# Sheet5.net
KiCad netlist of a schematic drawn in Altium Designer
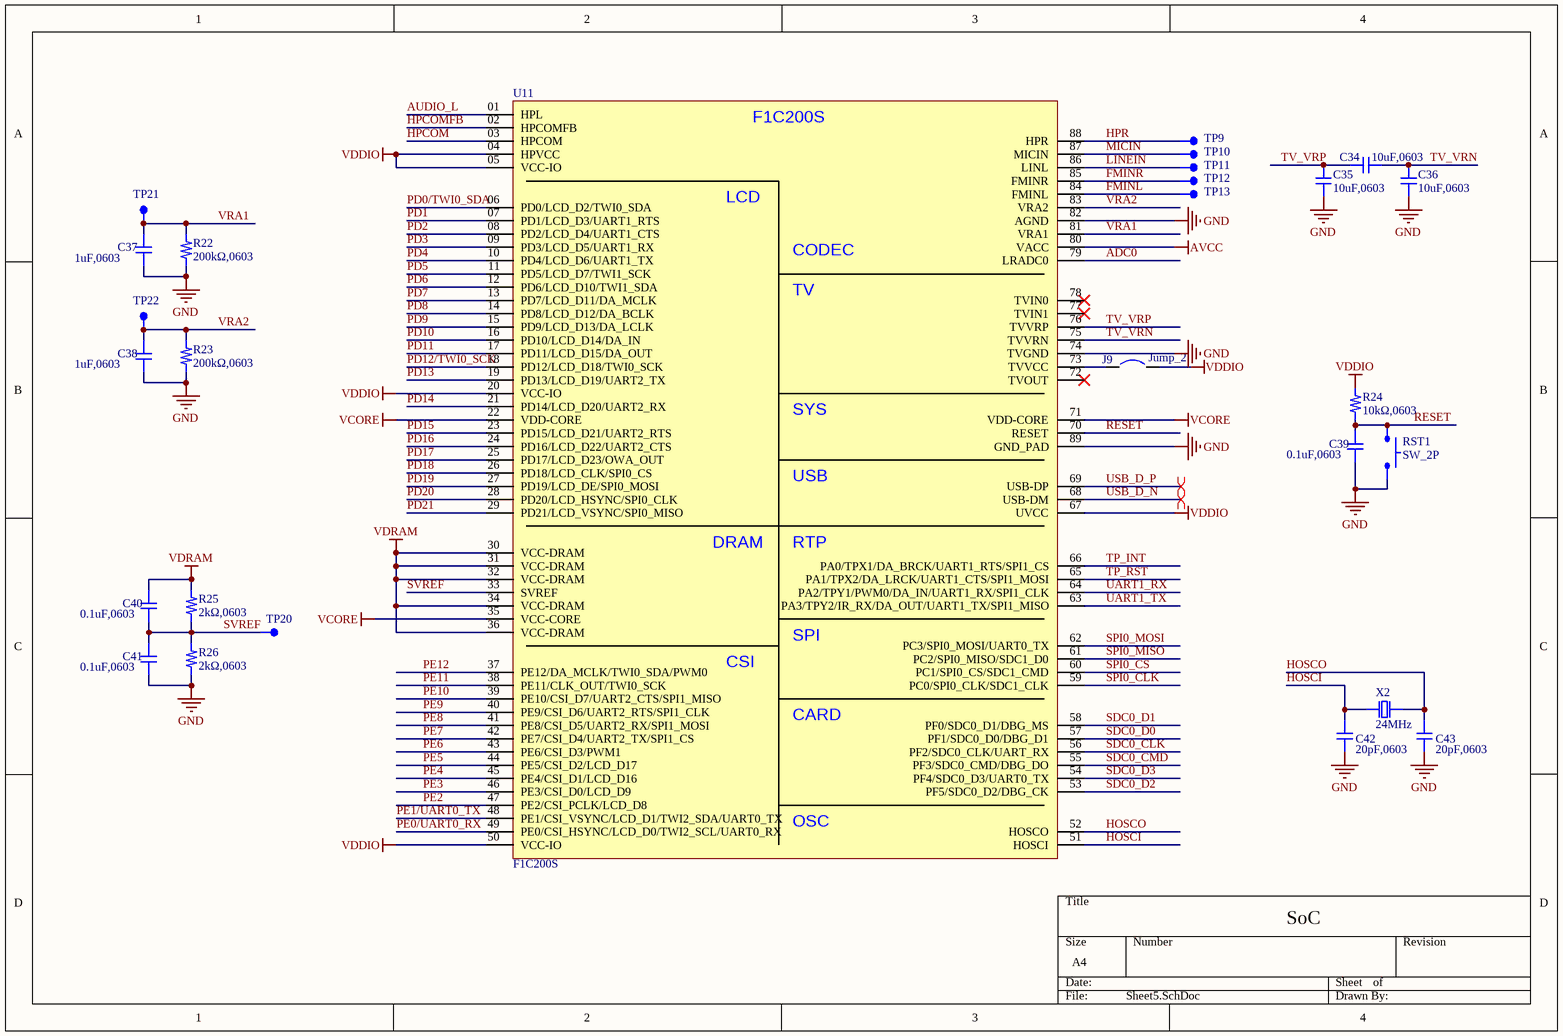
[diagram p0: Sheet5.SchDoc]

(export (version "E")
  (design (tool "Eeschema 10.0.6"))
  (components
    (comp (ref "C34") (value "10uF,0603") (footprint "C0603") (libsource (lib "myLib1") (part "Cap")))
    (comp (ref "C35") (value "10uF,0603") (footprint "C0603") (libsource (lib "myLib1") (part "Cap")))
    (comp (ref "C36") (value "10uF,0603") (footprint "C0603") (libsource (lib "myLib1") (part "Cap")))
    (comp (ref "C37") (value "1uF,0603") (footprint "C0603") (libsource (lib "myLib1") (part "Cap")))
    (comp (ref "C38") (value "1uF,0603") (footprint "C0603") (libsource (lib "myLib1") (part "Cap")))
    (comp (ref "C39") (value "0.1uF,0603") (footprint "C0603") (libsource (lib "myLib1") (part "Cap")))
    (comp (ref "C40") (value "0.1uF,0603") (footprint "C0603") (libsource (lib "myLib1") (part "Cap")))
    (comp (ref "C41") (value "0.1uF,0603") (footprint "C0603") (libsource (lib "myLib1") (part "Cap")))
    (comp (ref "C42") (value "20pF,0603") (footprint "C0603") (libsource (lib "myLib1") (part "Cap")))
    (comp (ref "C43") (value "20pF,0603") (footprint "C0603") (libsource (lib "myLib1") (part "Cap")))
    (comp (ref "J9") (value "Jump_2") (footprint "Jp_small") (libsource (lib "myLib1") (part "Jump_2")))
    (comp (ref "R22") (value "200kΩ,0603") (footprint "R0603") (libsource (lib "myLib1") (part "Res")))
    (comp (ref "R23") (value "200kΩ,0603") (footprint "R0603") (libsource (lib "myLib1") (part "Res")))
    (comp (ref "R24") (value "10kΩ,0603") (footprint "R0603") (libsource (lib "myLib1") (part "Res")))
    (comp (ref "R25") (value "2kΩ,0603") (footprint "R0603") (libsource (lib "myLib1") (part "Res")))
    (comp (ref "R26") (value "2kΩ,0603") (footprint "R0603") (libsource (lib "myLib1") (part "Res")))
    (comp (ref "RST1") (value "SW_2P") (footprint "SW_2P_4") (libsource (lib "myLib1") (part "SW_2P")))
    (comp (ref "TP9") (value "TP") (footprint "TP") (libsource (lib "myLib1") (part "TP")))
    (comp (ref "TP10") (value "TP") (footprint "TP") (libsource (lib "myLib1") (part "TP")))
    (comp (ref "TP11") (value "TP") (footprint "TP") (libsource (lib "myLib1") (part "TP")))
    (comp (ref "TP12") (value "TP") (footprint "TP") (libsource (lib "myLib1") (part "TP")))
    (comp (ref "TP13") (value "TP") (footprint "TP") (libsource (lib "myLib1") (part "TP")))
    (comp (ref "TP20") (value "TP") (footprint "TP") (libsource (lib "myLib1") (part "TP")))
    (comp (ref "TP21") (value "TP") (footprint "TP") (libsource (lib "myLib1") (part "TP")))
    (comp (ref "TP22") (value "TP") (footprint "TP") (libsource (lib "myLib1") (part "TP")))
    (comp (ref "U11")
      (value "F1C200S")
      (footprint "MQFN_10_10_v3")
      (libsource (lib "myLib1") (part "F1C200S"))
    )
    (comp (ref "X2") (value "24MHz") (footprint "XTAL_SMD_3225") (libsource (lib "myLib1") (part "XTAL")))
  )
  (nets
    (net (code "1") (name "/ADC0") (class "Default")
      (node (ref "U11") (pin "79") (pinfunction "LRADC0_79") (pintype "passive"))
    )
    (net (code "2") (name "/AUDIO_L") (class "Default")
      (node (ref "U11") (pin "01") (pinfunction "HPL_01") (pintype "passive"))
    )
    (net (code "3") (name "/FMINL") (class "Default")
      (node (ref "TP13") (pin "01") (pintype "passive"))
      (node (ref "U11") (pin "84") (pinfunction "FMINL_84") (pintype "passive"))
    )
    (net (code "4") (name "/FMINR") (class "Default")
      (node (ref "TP12") (pin "01") (pintype "passive"))
      (node (ref "U11") (pin "85") (pinfunction "FMINR_85") (pintype "passive"))
    )
    (net (code "5") (name "/HOSCI") (class "Default")
      (node (ref "C42") (pin "02") (pintype "passive"))
      (node (ref "U11") (pin "51") (pinfunction "HOSCI_51") (pintype "passive"))
      (node (ref "X2") (pin "01") (pinfunction "01_01") (pintype "passive"))
    )
    (net (code "6") (name "/HOSCO") (class "Default")
      (node (ref "C43") (pin "02") (pintype "passive"))
      (node (ref "U11") (pin "52") (pinfunction "HOSCO_52") (pintype "passive"))
      (node (ref "X2") (pin "02") (pinfunction "02_02") (pintype "passive"))
    )
    (net (code "7") (name "/HPCOM") (class "Default")
      (node (ref "U11") (pin "03") (pinfunction "HPCOM_03") (pintype "passive"))
    )
    (net (code "8") (name "/HPCOMFB") (class "Default")
      (node (ref "U11") (pin "02") (pinfunction "HPCOMFB_02") (pintype "passive"))
    )
    (net (code "9") (name "/HPR") (class "Default")
      (node (ref "TP9") (pin "01") (pintype "passive"))
      (node (ref "U11") (pin "88") (pinfunction "HPR_88") (pintype "passive"))
    )
    (net (code "10") (name "/LINEIN") (class "Default")
      (node (ref "TP11") (pin "01") (pintype "passive"))
      (node (ref "U11") (pin "86") (pinfunction "LINL_86") (pintype "passive"))
    )
    (net (code "11") (name "/MICIN") (class "Default")
      (node (ref "TP10") (pin "01") (pintype "passive"))
      (node (ref "U11") (pin "87") (pinfunction "MICIN_87") (pintype "passive"))
    )
    (net (code "12") (name "/PD0{slash}TWI0_SDA") (class "Default")
      (node (ref "U11") (pin "06") (pinfunction "PD0/LCD_D2/TWI0_SDA_06") (pintype "passive"))
    )
    (net (code "13") (name "/PD1") (class "Default")
      (node (ref "U11") (pin "07") (pinfunction "PD1/LCD_D3/UART1_RTS_07") (pintype "passive"))
    )
    (net (code "14") (name "/PD2") (class "Default")
      (node (ref "U11") (pin "08") (pinfunction "PD2/LCD_D4/UART1_CTS_08") (pintype "passive"))
    )
    (net (code "15") (name "/PD3") (class "Default")
      (node (ref "U11") (pin "09") (pinfunction "PD3/LCD_D5/UART1_RX_09") (pintype "passive"))
    )
    (net (code "16") (name "/PD4") (class "Default")
      (node (ref "U11") (pin "10") (pinfunction "PD4/LCD_D6/UART1_TX_10") (pintype "passive"))
    )
    (net (code "17") (name "/PD5") (class "Default")
      (node (ref "U11") (pin "11") (pinfunction "PD5/LCD_D7/TWI1_SCK_11") (pintype "passive"))
    )
    (net (code "18") (name "/PD6") (class "Default")
      (node (ref "U11") (pin "12") (pinfunction "PD6/LCD_D10/TWI1_SDA_12") (pintype "passive"))
    )
    (net (code "19") (name "/PD7") (class "Default")
      (node (ref "U11") (pin "13") (pinfunction "PD7/LCD_D11/DA_MCLK_13") (pintype "passive"))
    )
    (net (code "20") (name "/PD8") (class "Default")
      (node (ref "U11") (pin "14") (pinfunction "PD8/LCD_D12/DA_BCLK_14") (pintype "passive"))
    )
    (net (code "21") (name "/PD9") (class "Default")
      (node (ref "U11") (pin "15") (pinfunction "PD9/LCD_D13/DA_LCLK_15") (pintype "passive"))
    )
    (net (code "22") (name "/PD10") (class "Default")
      (node (ref "U11") (pin "16") (pinfunction "PD10/LCD_D14/DA_IN_16") (pintype "passive"))
    )
    (net (code "23") (name "/PD11") (class "Default")
      (node (ref "U11") (pin "17") (pinfunction "PD11/LCD_D15/DA_OUT_17") (pintype "passive"))
    )
    (net (code "24") (name "/PD12{slash}TWI0_SCK") (class "Default")
      (node (ref "U11") (pin "18") (pinfunction "PD12/LCD_D18/TWI0_SCK_18") (pintype "passive"))
    )
    (net (code "25") (name "/PD13") (class "Default")
      (node (ref "U11") (pin "19") (pinfunction "PD13/LCD_D19/UART2_TX_19") (pintype "passive"))
    )
    (net (code "26") (name "/PD14") (class "Default")
      (node (ref "U11") (pin "21") (pinfunction "PD14/LCD_D20/UART2_RX_21") (pintype "passive"))
    )
    (net (code "27") (name "/PD15") (class "Default")
      (node (ref "U11") (pin "23") (pinfunction "PD15/LCD_D21/UART2_RTS_23") (pintype "passive"))
    )
    (net (code "28") (name "/PD16") (class "Default")
      (node (ref "U11") (pin "24") (pinfunction "PD16/LCD_D22/UART2_CTS_24") (pintype "passive"))
    )
    (net (code "29") (name "/PD17") (class "Default")
      (node (ref "U11") (pin "25") (pinfunction "PD17/LCD_D23/OWA_OUT_25") (pintype "passive"))
    )
    (net (code "30") (name "/PD18") (class "Default")
      (node (ref "U11") (pin "26") (pinfunction "PD18/LCD_CLK/SPI0_CS_26") (pintype "passive"))
    )
    (net (code "31") (name "/PD19") (class "Default")
      (node (ref "U11") (pin "27") (pinfunction "PD19/LCD_DE/SPI0_MOSI_27") (pintype "passive"))
    )
    (net (code "32") (name "/PD20") (class "Default")
      (node (ref "U11") (pin "28") (pinfunction "PD20/LCD_HSYNC/SPI0_CLK_28") (pintype "passive"))
    )
    (net (code "33") (name "/PD21") (class "Default")
      (node (ref "U11") (pin "29") (pinfunction "PD21/LCD_VSYNC/SPI0_MISO_29") (pintype "passive"))
    )
    (net (code "34") (name "/PE0{slash}UART0_RX") (class "Default")
      (node (ref "U11") (pin "49") (pinfunction "PE0/CSI_HSYNC/LCD_D0/TWI2_SCL/UART0_RX_49") (pintype "passive"))
    )
    (net (code "35") (name "/PE1{slash}UART0_TX") (class "Default")
      (node (ref "U11") (pin "48") (pinfunction "PE1/CSI_VSYNC/LCD_D1/TWI2_SDA/UART0_TX_48") (pintype "passive"))
    )
    (net (code "36") (name "/PE2") (class "Default")
      (node (ref "U11") (pin "47") (pinfunction "PE2/CSI_PCLK/LCD_D8_47") (pintype "passive"))
    )
    (net (code "37") (name "/PE3") (class "Default")
      (node (ref "U11") (pin "46") (pinfunction "PE3/CSI_D0/LCD_D9_46") (pintype "passive"))
    )
    (net (code "38") (name "/PE4") (class "Default")
      (node (ref "U11") (pin "45") (pinfunction "PE4/CSI_D1/LCD_D16_45") (pintype "passive"))
    )
    (net (code "39") (name "/PE5") (class "Default")
      (node (ref "U11") (pin "44") (pinfunction "PE5/CSI_D2/LCD_D17_44") (pintype "passive"))
    )
    (net (code "40") (name "/PE6") (class "Default")
      (node (ref "U11") (pin "43") (pinfunction "PE6/CSI_D3/PWM1_43") (pintype "passive"))
    )
    (net (code "41") (name "/PE7") (class "Default")
      (node (ref "U11") (pin "42") (pinfunction "PE7/CSI_D4/UART2_TX/SPI1_CS_42") (pintype "passive"))
    )
    (net (code "42") (name "/PE8") (class "Default")
      (node (ref "U11") (pin "41") (pinfunction "PE8/CSI_D5/UART2_RX/SPI1_MOSI_41") (pintype "passive"))
    )
    (net (code "43") (name "/PE9") (class "Default")
      (node (ref "U11") (pin "40") (pinfunction "PE9/CSI_D6/UART2_RTS/SPI1_CLK_40") (pintype "passive"))
    )
    (net (code "44") (name "/PE10") (class "Default")
      (node (ref "U11") (pin "39") (pinfunction "PE10/CSI_D7/UART2_CTS/SPI1_MISO_39") (pintype "passive"))
    )
    (net (code "45") (name "/PE11") (class "Default")
      (node (ref "U11") (pin "38") (pinfunction "PE11/CLK_OUT/TWI0_SCK_38") (pintype "passive"))
    )
    (net (code "46") (name "/PE12") (class "Default")
      (node (ref "U11") (pin "37") (pinfunction "PE12/DA_MCLK/TWI0_SDA/PWM0_37") (pintype "passive"))
    )
    (net (code "47") (name "/RESET") (class "Default")
      (node (ref "C39") (pin "02") (pintype "passive"))
      (node (ref "R24") (pin "02") (pintype "passive"))
      (node (ref "RST1") (pin "01") (pintype "passive"))
      (node (ref "U11") (pin "70") (pinfunction "RESET_70") (pintype "passive"))
    )
    (net (code "48") (name "/SDC0_CLK") (class "Default")
      (node (ref "U11") (pin "56") (pinfunction "PF2/SDC0_CLK/UART_RX_56") (pintype "passive"))
    )
    (net (code "49") (name "/SDC0_CMD") (class "Default")
      (node (ref "U11") (pin "55") (pinfunction "PF3/SDC0_CMD/DBG_DO_55") (pintype "passive"))
    )
    (net (code "50") (name "/SDC0_D0") (class "Default")
      (node (ref "U11") (pin "57") (pinfunction "PF1/SDC0_D0/DBG_D1_57") (pintype "passive"))
    )
    (net (code "51") (name "/SDC0_D1") (class "Default")
      (node (ref "U11") (pin "58") (pinfunction "PF0/SDC0_D1/DBG_MS_58") (pintype "passive"))
    )
    (net (code "52") (name "/SDC0_D2") (class "Default")
      (node (ref "U11") (pin "53") (pinfunction "PF5/SDC0_D2/DBG_CK_53") (pintype "passive"))
    )
    (net (code "53") (name "/SDC0_D3") (class "Default")
      (node (ref "U11") (pin "54") (pinfunction "PF4/SDC0_D3/UART0_TX_54") (pintype "passive"))
    )
    (net (code "54") (name "/SPI0_CLK") (class "Default")
      (node (ref "U11") (pin "59") (pinfunction "PC0/SPI0_CLK/SDC1_CLK_59") (pintype "passive"))
    )
    (net (code "55") (name "/SPI0_CS") (class "Default")
      (node (ref "U11") (pin "60") (pinfunction "PC1/SPI0_CS/SDC1_CMD_60") (pintype "passive"))
    )
    (net (code "56") (name "/SPI0_MISO") (class "Default")
      (node (ref "U11") (pin "61") (pinfunction "PC2/SPI0_MISO/SDC1_D0_61") (pintype "passive"))
    )
    (net (code "57") (name "/SPI0_MOSI") (class "Default")
      (node (ref "U11") (pin "62") (pinfunction "PC3/SPI0_MOSI/UART0_TX_62") (pintype "passive"))
    )
    (net (code "58") (name "/SVREF") (class "Default")
      (node (ref "C40") (pin "01") (pintype "passive"))
      (node (ref "C41") (pin "02") (pintype "passive"))
      (node (ref "R25") (pin "02") (pintype "passive"))
      (node (ref "R26") (pin "01") (pintype "passive"))
      (node (ref "TP20") (pin "01") (pintype "passive"))
      (node (ref "U11") (pin "33") (pinfunction "SVREF_33") (pintype "passive"))
    )
    (net (code "59") (name "/TP_INT") (class "Default")
      (node (ref "U11") (pin "66") (pinfunction "PA0/TPX1/DA_BRCK/UART1_RTS/SPI1_CS_66") (pintype "passive"))
    )
    (net (code "60") (name "/TP_RST") (class "Default")
      (node (ref "U11") (pin "65") (pinfunction "PA1/TPX2/DA_LRCK/UART1_CTS/SPI1_MOSI_65") (pintype "passive"))
    )
    (net (code "61") (name "/TV_VRN") (class "Default")
      (node (ref "C34") (pin "01") (pintype "passive"))
      (node (ref "C36") (pin "01") (pintype "passive"))
      (node (ref "U11") (pin "75") (pinfunction "TVVRN_75") (pintype "passive"))
    )
    (net (code "62") (name "/TV_VRP") (class "Default")
      (node (ref "C34") (pin "02") (pintype "passive"))
      (node (ref "C35") (pin "01") (pintype "passive"))
      (node (ref "U11") (pin "76") (pinfunction "TVVRP_76") (pintype "passive"))
    )
    (net (code "63") (name "/UART1_RX") (class "Default")
      (node (ref "U11") (pin "64") (pinfunction "PA2/TPY1/PWM0/DA_IN/UART1_RX/SPI1_CLK_64") (pintype "passive"))
    )
    (net (code "64") (name "/UART1_TX") (class "Default")
      (node (ref "U11") (pin "63") (pinfunction "PA3/TPY2/IR_RX/DA_OUT/UART1_TX/SPI1_MISO_63") (pintype "passive"))
    )
    (net (code "65") (name "/USB_D_N") (class "Default")
      (node (ref "U11") (pin "68") (pinfunction "USB-DM_68") (pintype "passive"))
    )
    (net (code "66") (name "/USB_D_P") (class "Default")
      (node (ref "U11") (pin "69") (pinfunction "USB-DP_69") (pintype "passive"))
    )
    (net (code "67") (name "/VRA1") (class "Default")
      (node (ref "C37") (pin "02") (pintype "passive"))
      (node (ref "R22") (pin "01") (pintype "passive"))
      (node (ref "TP21") (pin "01") (pintype "passive"))
      (node (ref "U11") (pin "81") (pinfunction "VRA1_81") (pintype "passive"))
    )
    (net (code "68") (name "/VRA2") (class "Default")
      (node (ref "C38") (pin "02") (pintype "passive"))
      (node (ref "R23") (pin "01") (pintype "passive"))
      (node (ref "TP22") (pin "01") (pintype "passive"))
      (node (ref "U11") (pin "83") (pinfunction "VRA2_83") (pintype "passive"))
    )
    (net (code "69") (name "AVCC") (class "Default")
      (node (ref "U11") (pin "80") (pinfunction "VACC_80") (pintype "passive"))
    )
    (net (code "70") (name "GND") (class "Default")
      (node (ref "C35") (pin "02") (pintype "passive"))
      (node (ref "C36") (pin "02") (pintype "passive"))
      (node (ref "C37") (pin "01") (pintype "passive"))
      (node (ref "C38") (pin "01") (pintype "passive"))
      (node (ref "C39") (pin "01") (pintype "passive"))
      (node (ref "C41") (pin "01") (pintype "passive"))
      (node (ref "C42") (pin "01") (pintype "passive"))
      (node (ref "C43") (pin "01") (pintype "passive"))
      (node (ref "R22") (pin "02") (pintype "passive"))
      (node (ref "R23") (pin "02") (pintype "passive"))
      (node (ref "R26") (pin "02") (pintype "passive"))
      (node (ref "RST1") (pin "02") (pintype "passive"))
      (node (ref "U11") (pin "74") (pinfunction "TVGND_74") (pintype "passive"))
      (node (ref "U11") (pin "82") (pinfunction "AGND_82") (pintype "passive"))
      (node (ref "U11") (pin "89") (pinfunction "GND_PAD_89") (pintype "passive"))
    )
    (net (code "71") (name "Net-(J9-1)") (class "Default")
      (node (ref "J9") (pin "01") (pinfunction "1_01") (pintype "passive"))
      (node (ref "U11") (pin "73") (pinfunction "TVVCC_73") (pintype "passive"))
    )
    (net (code "72") (name "VCORE") (class "Default")
      (node (ref "U11") (pin "22") (pinfunction "VDD-CORE_22") (pintype "passive"))
      (node (ref "U11") (pin "35") (pinfunction "VCC-CORE_35") (pintype "passive"))
      (node (ref "U11") (pin "71") (pinfunction "VDD-CORE_71") (pintype "passive"))
    )
    (net (code "73") (name "VDDIO") (class "Default")
      (node (ref "J9") (pin "02") (pinfunction "2_02") (pintype "passive"))
      (node (ref "R24") (pin "01") (pintype "passive"))
      (node (ref "U11") (pin "04") (pinfunction "HPVCC_04") (pintype "passive"))
      (node (ref "U11") (pin "05") (pinfunction "VCC-IO_05") (pintype "passive"))
      (node (ref "U11") (pin "20") (pinfunction "VCC-IO_20") (pintype "passive"))
      (node (ref "U11") (pin "50") (pinfunction "VCC-IO_50") (pintype "passive"))
      (node (ref "U11") (pin "67") (pinfunction "UVCC_67") (pintype "passive"))
    )
    (net (code "74") (name "VDRAM") (class "Default")
      (node (ref "C40") (pin "02") (pintype "passive"))
      (node (ref "R25") (pin "01") (pintype "passive"))
      (node (ref "U11") (pin "30") (pinfunction "VCC-DRAM_30") (pintype "passive"))
      (node (ref "U11") (pin "31") (pinfunction "VCC-DRAM_31") (pintype "passive"))
      (node (ref "U11") (pin "32") (pinfunction "VCC-DRAM_32") (pintype "passive"))
      (node (ref "U11") (pin "34") (pinfunction "VCC-DRAM_34") (pintype "passive"))
      (node (ref "U11") (pin "36") (pinfunction "VCC-DRAM_36") (pintype "passive"))
    )
    (net (code "75") (name "unconnected-(U11-TVIN0-Pad78)") (class "Default")
      (node (ref "U11") (pin "78") (pinfunction "TVIN0_78") (pintype "passive+no_connect"))
    )
    (net (code "76") (name "unconnected-(U11-TVIN1-Pad77)") (class "Default")
      (node (ref "U11") (pin "77") (pinfunction "TVIN1_77") (pintype "passive+no_connect"))
    )
    (net (code "77") (name "unconnected-(U11-TVOUT-Pad72)") (class "Default")
      (node (ref "U11") (pin "72") (pinfunction "TVOUT_72") (pintype "passive+no_connect"))
    )
  )
)
